# PiInTheSky-Mainboard-v2_3.net
KiCad netlist of a schematic drawn in EAGLE
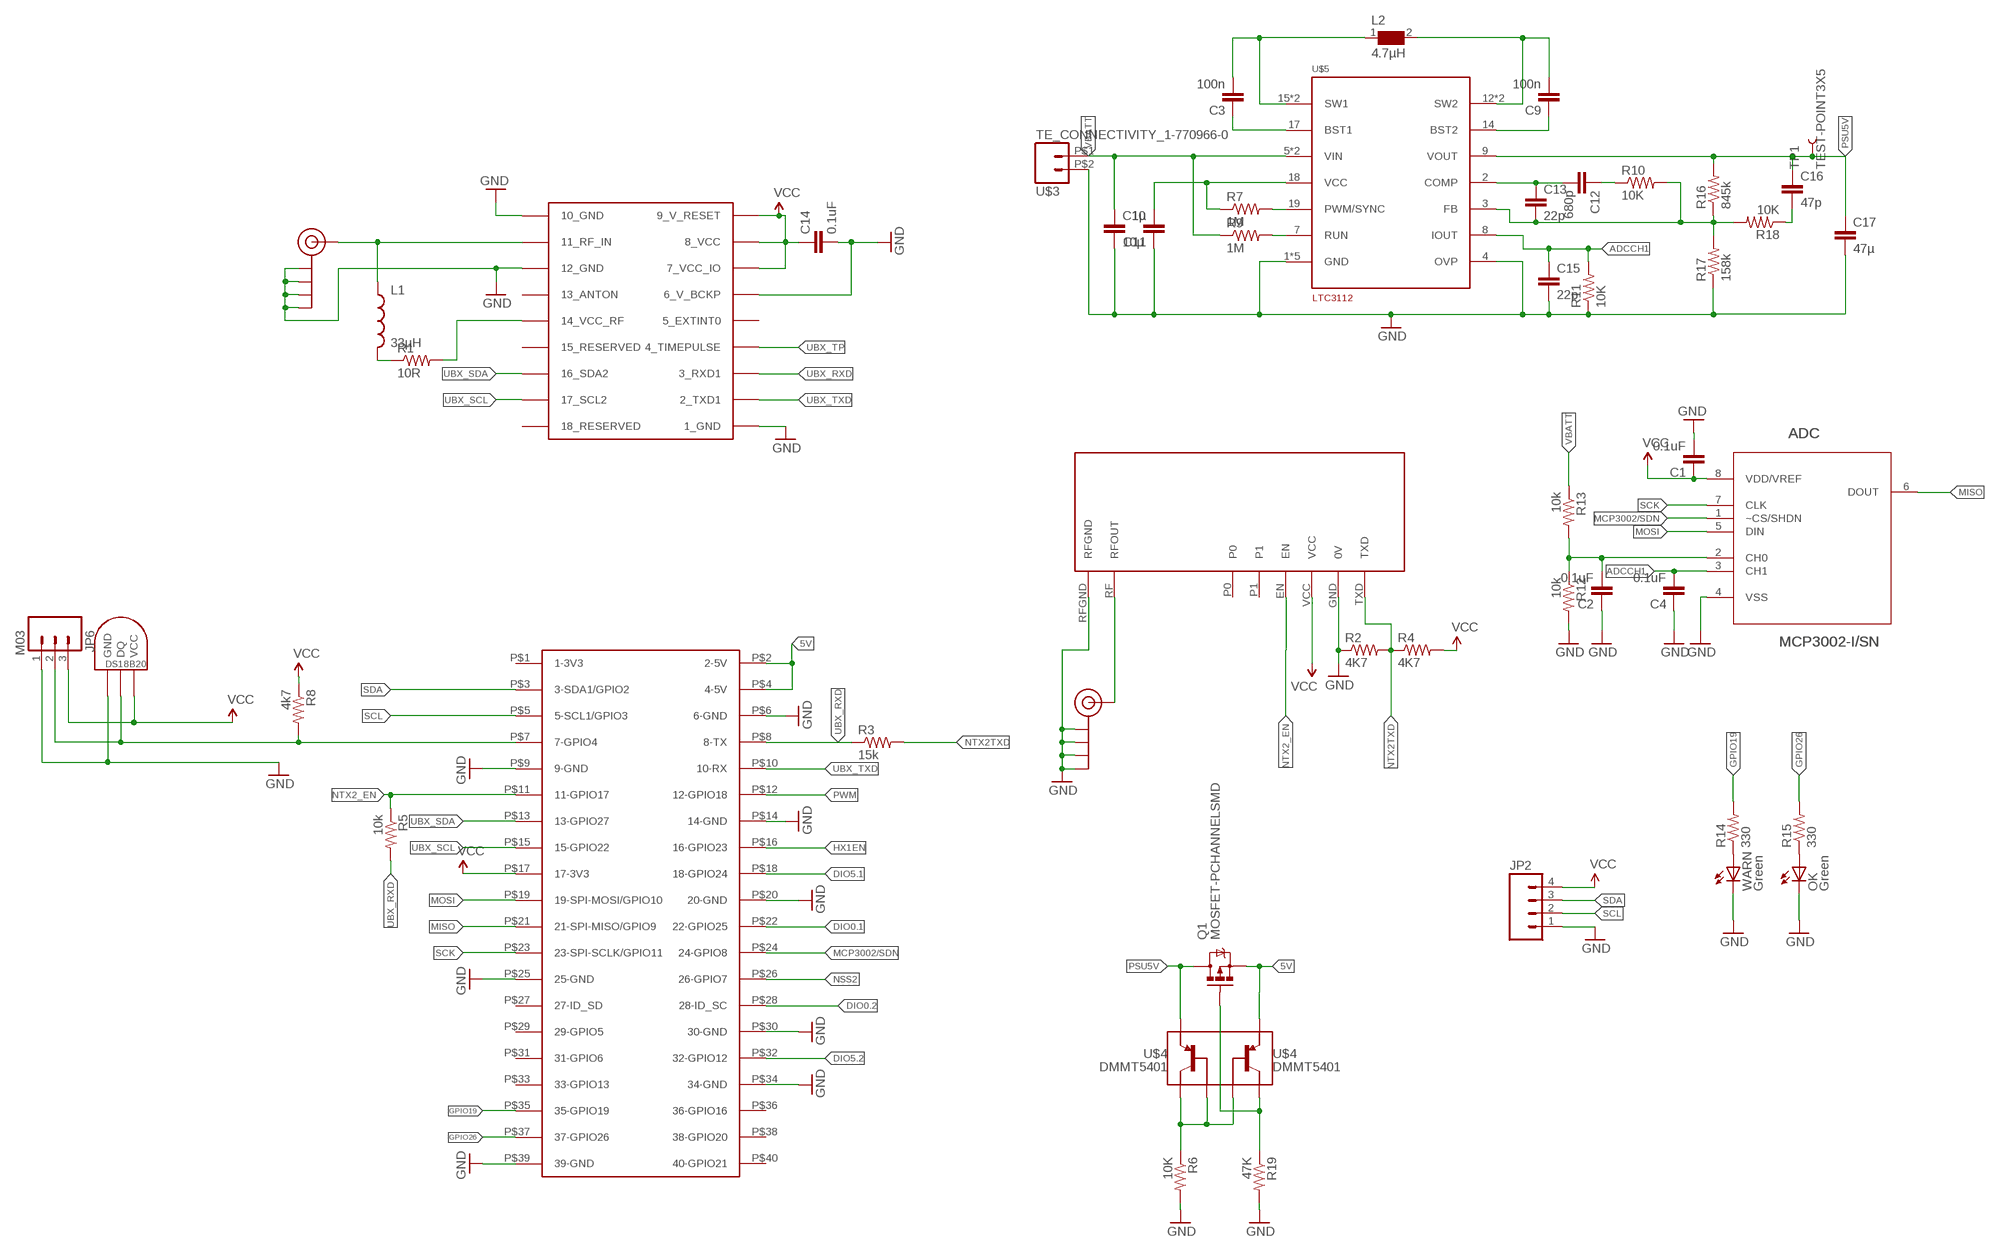
[diagram p0: schematic, sheet 1]

(export (version "E")
  (design (tool "Eeschema 10.0.6"))
  (components
    (comp (ref "ADC")
      (value "MCP3002-I/SN")
      (footprint "eagle-import:SOIC127P600X175-8N")
      (libsource (lib "eagle-import") (part "MCP3002-I/SN"))
    )
    (comp (ref "C1")
      (value "0.1uF")
      (footprint "eagle-import:0603-CAP")
      (libsource (lib "eagle-import") (part "CAP0603-CAP"))
    )
    (comp (ref "C2")
      (value "0.1uF")
      (footprint "eagle-import:0603-CAP")
      (libsource (lib "eagle-import") (part "CAP0603-CAP"))
    )
    (comp (ref "C3")
      (value "100n")
      (footprint "eagle-import:0603-CAP")
      (libsource (lib "eagle-import") (part "CAP0603-CAP"))
    )
    (comp (ref "C4")
      (value "0.1uF")
      (footprint "eagle-import:0603-CAP")
      (libsource (lib "eagle-import") (part "CAP0603-CAP"))
    )
    (comp (ref "C9")
      (value "100n")
      (footprint "eagle-import:0603-CAP")
      (libsource (lib "eagle-import") (part "CAP0603-CAP"))
    )
    (comp (ref "C10")
      (value "10µ")
      (footprint "eagle-import:1206")
      (libsource (lib "eagle-import") (part "CAP1206"))
    )
    (comp (ref "C11")
      (value "1µ")
      (footprint "eagle-import:0603-CAP")
      (libsource (lib "eagle-import") (part "CAP0603-CAP"))
    )
    (comp (ref "C12")
      (value "680p")
      (footprint "eagle-import:0603-CAP")
      (libsource (lib "eagle-import") (part "CAP0603-CAP"))
    )
    (comp (ref "C13")
      (value "22p")
      (footprint "eagle-import:0603-CAP")
      (libsource (lib "eagle-import") (part "CAP0603-CAP"))
    )
    (comp (ref "C14")
      (value "0.1uF")
      (footprint "eagle-import:0603-CAP")
      (libsource (lib "eagle-import") (part "CAP0603-CAP"))
    )
    (comp (ref "C15")
      (value "22p")
      (footprint "eagle-import:0603-CAP")
      (libsource (lib "eagle-import") (part "CAP0603-CAP"))
    )
    (comp (ref "C16")
      (value "47p")
      (footprint "eagle-import:0603-CAP")
      (libsource (lib "eagle-import") (part "CAP0603-CAP"))
    )
    (comp (ref "C17")
      (value "47µ")
      (footprint "eagle-import:1206")
      (libsource (lib "eagle-import") (part "CAP1206"))
    )
    (comp (ref "J$1")
      (value "SMA_EDGE")
      (footprint "eagle-import:SMA-EDGE")
      (libsource (lib "eagle-import") (part "SMA_EDGE"))
    )
    (comp (ref "J$2")
      (value "SMA_EDGE")
      (footprint "eagle-import:SMA-EDGE")
      (libsource (lib "eagle-import") (part "SMA_EDGE"))
    )
    (comp (ref "JP2")
      (value "M04PTH")
      (footprint "eagle-import:1X04")
      (libsource (lib "eagle-import") (part "M04PTH"))
    )
    (comp (ref "JP6")
      (value "M03")
      (footprint "eagle-import:M03-JST")
      (libsource (lib "eagle-import") (part "M03"))
    )
    (comp (ref "L1")
      (value "33µH")
      (footprint "eagle-import:0603")
      (libsource (lib "eagle-import") (part "INDUCTOR0603"))
    )
    (comp (ref "L2")
      (value "4.7µH")
      (footprint "eagle-import:WE-HCI_7030_7040_7050")
      (fields (field (name "MPN") "744311470"))
      (libsource (lib "eagle-import") (part "WE-HCI_7030/7040/7050-744311470"))
    )
    (comp (ref "OK")
      (value "Green")
      (footprint "eagle-import:LED-0603")
      (libsource (lib "eagle-import") (part "LED0603"))
    )
    (comp (ref "Q1")
      (value "MOSFET-PCHANNELSMD")
      (footprint "eagle-import:SOT23-3")
      (libsource (lib "eagle-import") (part "MOSFET-PCHANNELSMD"))
    )
    (comp (ref "R1")
      (value "10R")
      (footprint "eagle-import:0603-RES")
      (libsource (lib "eagle-import") (part "RESISTOR0603-RES"))
    )
    (comp (ref "R2")
      (value "4K7")
      (footprint "eagle-import:0603-RES")
      (libsource (lib "eagle-import") (part "RESISTOR0603-RES"))
    )
    (comp (ref "R3")
      (value "15k")
      (footprint "eagle-import:0603-RES")
      (libsource (lib "eagle-import") (part "RESISTOR0603-RES"))
    )
    (comp (ref "R4")
      (value "4K7")
      (footprint "eagle-import:0603-RES")
      (libsource (lib "eagle-import") (part "RESISTOR0603-RES"))
    )
    (comp (ref "R5")
      (value "10k")
      (footprint "eagle-import:0603-RES")
      (libsource (lib "eagle-import") (part "RESISTOR0603-RES"))
    )
    (comp (ref "R6")
      (value "10K")
      (footprint "eagle-import:0603-RES")
      (libsource (lib "eagle-import") (part "RESISTOR0603-RES"))
    )
    (comp (ref "R7")
      (value "1M")
      (footprint "eagle-import:0603-RES")
      (libsource (lib "eagle-import") (part "RESISTOR0603-RES"))
    )
    (comp (ref "R8")
      (value "4k7")
      (footprint "eagle-import:0603-RES")
      (libsource (lib "eagle-import") (part "RESISTOR0603-RES"))
    )
    (comp (ref "R9")
      (value "1M")
      (footprint "eagle-import:0603-RES")
      (libsource (lib "eagle-import") (part "RESISTOR0603-RES"))
    )
    (comp (ref "R10")
      (value "10K")
      (footprint "eagle-import:0603-RES")
      (libsource (lib "eagle-import") (part "RESISTOR0603-RES"))
    )
    (comp (ref "R11")
      (value "10K")
      (footprint "eagle-import:0603-RES")
      (libsource (lib "eagle-import") (part "RESISTOR0603-RES"))
    )
    (comp (ref "R12")
      (value "10k")
      (footprint "eagle-import:0603-RES")
      (libsource (lib "eagle-import") (part "RESISTOR0603-RES"))
    )
    (comp (ref "R13")
      (value "10k")
      (footprint "eagle-import:0603-RES")
      (libsource (lib "eagle-import") (part "RESISTOR0603-RES"))
    )
    (comp (ref "R14")
      (value "330")
      (footprint "eagle-import:0603-RES")
      (libsource (lib "eagle-import") (part "RESISTOR0603-RES"))
    )
    (comp (ref "R15")
      (value "330")
      (footprint "eagle-import:0603-RES")
      (libsource (lib "eagle-import") (part "RESISTOR0603-RES"))
    )
    (comp (ref "R16")
      (value "845k")
      (footprint "eagle-import:0603-RES")
      (libsource (lib "eagle-import") (part "RESISTOR0603-RES"))
    )
    (comp (ref "R17")
      (value "158k")
      (footprint "eagle-import:0603-RES")
      (libsource (lib "eagle-import") (part "RESISTOR0603-RES"))
    )
    (comp (ref "R18")
      (value "10K")
      (footprint "eagle-import:0603-RES")
      (libsource (lib "eagle-import") (part "RESISTOR0603-RES"))
    )
    (comp (ref "R19")
      (value "47K")
      (footprint "eagle-import:0603-RES")
      (libsource (lib "eagle-import") (part "RESISTOR0603-RES"))
    )
    (comp (ref "TEMP")
      (value "DS1821")
      (footprint "eagle-import:DS18B20_SOIC")
      (libsource (lib "eagle-import") (part "DS1820SOIC"))
    )
    (comp (ref "TP1")
      (value "TEST-POINT3X5")
      (footprint "eagle-import:PAD.03X.05")
      (libsource (lib "eagle-import") (part "TEST-POINT3X5"))
    )
    (comp (ref "U$1")
      (value "RASPBERRY-PI+")
      (footprint "eagle-import:RASPBERRY-PI-PLUS-CAM_NOTCH")
      (libsource (lib "eagle-import") (part "RASPBERRY-PI+"))
    )
    (comp (ref "U$3")
      (value "TE_CONNECTIVITY_1-770966-0")
      (footprint "eagle-import:TE_CONNECTIVITY_1-770966-0")
      (libsource (lib "eagle-import") (part "TE_CONNECTIVITY_1-770966-0"))
    )
    (comp (ref "U$4")
      (value "DMMT5401")
      (footprint "eagle-import:SOT26")
      (libsource (lib "eagle-import") (part "DMMT5401"))
    )
    (comp (ref "U$5")
      (value "LTC3112")
      (footprint "eagle-import:TSSOP-20")
      (libsource (lib "eagle-import") (part "LTC3112"))
    )
    (comp (ref "U$7")
      (value "UBLOX_MAX")
      (footprint "eagle-import:UBLOX_MAX")
      (libsource (lib "eagle-import") (part "UBLOX_MAX"))
    )
    (comp (ref "U$8")
      (value "RADIOMETRIX-MTX2")
      (footprint "eagle-import:RADIOMETRIX-MTX2")
      (libsource (lib "eagle-import") (part "RADIOMETRIX-MTX2"))
    )
    (comp (ref "WARN")
      (value "Green")
      (footprint "eagle-import:LED-0603")
      (libsource (lib "eagle-import") (part "LED0603"))
    )
  )
  (nets
    (net (code "1") (name "5V") (class "Default")
      (node (ref "Q1") (pin "2") (pinfunction "S_2") (pintype "passive"))
      (node (ref "U$1") (pin "P$2") (pinfunction "2-5V_P$2") (pintype "bidirectional"))
      (node (ref "U$1") (pin "P$4") (pinfunction "4-5V_P$4") (pintype "bidirectional"))
      (node (ref "U$4") (pin "5") (pinfunction "E2_5") (pintype "passive"))
    )
    (net (code "2") (name "ADCCH1") (class "Default")
      (node (ref "ADC") (pin "3") (pinfunction "CH1_3") (pintype "input"))
      (node (ref "C15") (pin "1") (pinfunction "1_1") (pintype "passive"))
      (node (ref "C4") (pin "2") (pinfunction "2_2") (pintype "passive"))
      (node (ref "R11") (pin "2") (pinfunction "2_2") (pintype "passive"))
      (node (ref "U$5") (pin "8") (pinfunction "IOUT_8") (pintype "bidirectional"))
    )
    (net (code "3") (name "DIO0.1") (class "Default")
      (node (ref "U$1") (pin "P$22") (pinfunction "22-GPIO25_P$22") (pintype "bidirectional"))
    )
    (net (code "4") (name "DIO0.2") (class "Default")
      (node (ref "U$1") (pin "P$28") (pinfunction "28-ID_SC_P$28") (pintype "bidirectional"))
    )
    (net (code "5") (name "DIO5.1") (class "Default")
      (node (ref "U$1") (pin "P$18") (pinfunction "18-GPIO24_P$18") (pintype "bidirectional"))
    )
    (net (code "6") (name "DIO5.2") (class "Default")
      (node (ref "U$1") (pin "P$32") (pinfunction "32-GPIO12_P$32") (pintype "bidirectional"))
    )
    (net (code "7") (name "GND") (class "Default")
      (node (ref "ADC") (pin "4") (pinfunction "VSS_4") (pintype "power_in"))
      (node (ref "C1") (pin "2") (pinfunction "2_2") (pintype "passive"))
      (node (ref "C10") (pin "2") (pinfunction "2_2") (pintype "passive"))
      (node (ref "C11") (pin "1") (pinfunction "1_1") (pintype "passive"))
      (node (ref "C14") (pin "2") (pinfunction "2_2") (pintype "passive"))
      (node (ref "C15") (pin "2") (pinfunction "2_2") (pintype "passive"))
      (node (ref "C17") (pin "2") (pinfunction "2_2") (pintype "passive"))
      (node (ref "C2") (pin "1") (pinfunction "1_1") (pintype "passive"))
      (node (ref "C4") (pin "1") (pinfunction "1_1") (pintype "passive"))
      (node (ref "J$1") (pin "GND@0") (pinfunction "GND_GND@0") (pintype "bidirectional"))
      (node (ref "J$1") (pin "GND@1") (pinfunction "GND_GND@1") (pintype "bidirectional"))
      (node (ref "J$1") (pin "GND@2") (pinfunction "GND_GND@2") (pintype "bidirectional"))
      (node (ref "J$1") (pin "GND@3") (pinfunction "GND_GND@3") (pintype "bidirectional"))
      (node (ref "J$2") (pin "GND@0") (pinfunction "GND_GND@0") (pintype "bidirectional"))
      (node (ref "J$2") (pin "GND@1") (pinfunction "GND_GND@1") (pintype "bidirectional"))
      (node (ref "J$2") (pin "GND@2") (pinfunction "GND_GND@2") (pintype "bidirectional"))
      (node (ref "J$2") (pin "GND@3") (pinfunction "GND_GND@3") (pintype "bidirectional"))
      (node (ref "JP2") (pin "1") (pinfunction "1_1") (pintype "passive"))
      (node (ref "JP6") (pin "1") (pinfunction "1_1") (pintype "passive"))
      (node (ref "OK") (pin "C") (pinfunction "C_C") (pintype "passive"))
      (node (ref "R11") (pin "1") (pinfunction "1_1") (pintype "passive"))
      (node (ref "R12") (pin "2") (pinfunction "2_2") (pintype "passive"))
      (node (ref "R17") (pin "1") (pinfunction "1_1") (pintype "passive"))
      (node (ref "R19") (pin "2") (pinfunction "2_2") (pintype "passive"))
      (node (ref "R2") (pin "1") (pinfunction "1_1") (pintype "passive"))
      (node (ref "R6") (pin "2") (pinfunction "2_2") (pintype "passive"))
      (node (ref "TEMP") (pin "GND") (pinfunction "GND_GND") (pintype "power_in"))
      (node (ref "U$1") (pin "P$14") (pinfunction "14-GND_P$14") (pintype "bidirectional"))
      (node (ref "U$1") (pin "P$20") (pinfunction "20-GND_P$20") (pintype "bidirectional"))
      (node (ref "U$1") (pin "P$25") (pinfunction "25-GND_P$25") (pintype "bidirectional"))
      (node (ref "U$1") (pin "P$30") (pinfunction "30-GND_P$30") (pintype "bidirectional"))
      (node (ref "U$1") (pin "P$34") (pinfunction "34-GND_P$34") (pintype "bidirectional"))
      (node (ref "U$1") (pin "P$39") (pinfunction "39-GND_P$39") (pintype "bidirectional"))
      (node (ref "U$1") (pin "P$6") (pinfunction "6-GND_P$6") (pintype "bidirectional"))
      (node (ref "U$1") (pin "P$9") (pinfunction "9-GND_P$9") (pintype "bidirectional"))
      (node (ref "U$3") (pin "P$2") (pinfunction "2_P$2") (pintype "passive"))
      (node (ref "U$5") (pin "1") (pinfunction "GND_1") (pintype "bidirectional"))
      (node (ref "U$5") (pin "10") (pinfunction "GND_10") (pintype "bidirectional"))
      (node (ref "U$5") (pin "11") (pinfunction "GND_11") (pintype "bidirectional"))
      (node (ref "U$5") (pin "20") (pinfunction "GND_20") (pintype "bidirectional"))
      (node (ref "U$5") (pin "21") (pinfunction "GND_21") (pintype "bidirectional"))
      (node (ref "U$5") (pin "4") (pinfunction "OVP_4") (pintype "bidirectional"))
      (node (ref "U$7") (pin "10_GND") (pinfunction "10_GND_10_GND") (pintype "power_in"))
      (node (ref "U$7") (pin "12_GND") (pinfunction "12_GND_12_GND") (pintype "power_in"))
      (node (ref "U$7") (pin "1_GND") (pinfunction "1_GND_1_GND") (pintype "power_in"))
      (node (ref "U$7") (pin "6_V_BCKP") (pinfunction "6_V_BCKP_6_V_BCKP") (pintype "bidirectional"))
      (node (ref "U$8") (pin "GND") (pinfunction "0V_GND") (pintype "bidirectional"))
      (node (ref "U$8") (pin "RFGND") (pinfunction "RFGND_RFGND") (pintype "bidirectional"))
      (node (ref "WARN") (pin "C") (pinfunction "C_C") (pintype "passive"))
    )
    (net (code "8") (name "GPIO19") (class "Default")
      (node (ref "R14") (pin "2") (pinfunction "2_2") (pintype "passive"))
      (node (ref "U$1") (pin "P$35") (pinfunction "35-GPIO19_P$35") (pintype "bidirectional"))
    )
    (net (code "9") (name "GPIO26") (class "Default")
      (node (ref "R15") (pin "2") (pinfunction "2_2") (pintype "passive"))
      (node (ref "U$1") (pin "P$37") (pinfunction "37-GPIO26_P$37") (pintype "bidirectional"))
    )
    (net (code "10") (name "HX1EN") (class "Default")
      (node (ref "U$1") (pin "P$16") (pinfunction "16-GPIO23_P$16") (pintype "bidirectional"))
    )
    (net (code "11") (name "MCP3002{slash}SDN") (class "Default")
      (node (ref "ADC") (pin "1") (pinfunction "~{CS/SHDN}_1") (pintype "input"))
      (node (ref "U$1") (pin "P$24") (pinfunction "24-GPIO8_P$24") (pintype "bidirectional"))
    )
    (net (code "12") (name "MISO") (class "Default")
      (node (ref "ADC") (pin "6") (pinfunction "DOUT_6") (pintype "output"))
      (node (ref "U$1") (pin "P$21") (pinfunction "21-SPI-MISO/GPIO9_P$21") (pintype "bidirectional"))
    )
    (net (code "13") (name "MOSI") (class "Default")
      (node (ref "ADC") (pin "5") (pinfunction "DIN_5") (pintype "input"))
      (node (ref "U$1") (pin "P$19") (pinfunction "19-SPI-MOSI/GPIO10_P$19") (pintype "bidirectional"))
    )
    (net (code "14") (name "NSS2") (class "Default")
      (node (ref "U$1") (pin "P$26") (pinfunction "26-GPIO7_P$26") (pintype "bidirectional"))
    )
    (net (code "15") (name "NTX2TXD") (class "Default")
      (node (ref "R2") (pin "2") (pinfunction "2_2") (pintype "passive"))
      (node (ref "R3") (pin "2") (pinfunction "2_2") (pintype "passive"))
      (node (ref "R4") (pin "1") (pinfunction "1_1") (pintype "passive"))
      (node (ref "U$8") (pin "TXD") (pinfunction "TXD_TXD") (pintype "bidirectional"))
    )
    (net (code "16") (name "NTX2_EN") (class "Default")
      (node (ref "R5") (pin "1") (pinfunction "1_1") (pintype "passive"))
      (node (ref "U$1") (pin "P$11") (pinfunction "11-GPIO17_P$11") (pintype "bidirectional"))
      (node (ref "U$8") (pin "EN") (pinfunction "EN_EN") (pintype "bidirectional"))
    )
    (net (code "17") (name "Net-(ADC-CH0)") (class "Default")
      (node (ref "ADC") (pin "2") (pinfunction "CH0_2") (pintype "input"))
      (node (ref "C2") (pin "2") (pinfunction "2_2") (pintype "passive"))
      (node (ref "R12") (pin "1") (pinfunction "1_1") (pintype "passive"))
      (node (ref "R13") (pin "2") (pinfunction "2_2") (pintype "passive"))
    )
    (net (code "18") (name "Net-(C3-Pad2)") (class "Default")
      (node (ref "C3") (pin "2") (pinfunction "2_2") (pintype "passive"))
      (node (ref "L2") (pin "1") (pinfunction "1_1") (pintype "passive"))
      (node (ref "U$5") (pin "15") (pinfunction "SW1_15") (pintype "bidirectional"))
      (node (ref "U$5") (pin "16") (pinfunction "SW1_16") (pintype "bidirectional"))
    )
    (net (code "19") (name "Net-(C9-Pad2)") (class "Default")
      (node (ref "C9") (pin "2") (pinfunction "2_2") (pintype "passive"))
      (node (ref "L2") (pin "2") (pinfunction "2_2") (pintype "passive"))
      (node (ref "U$5") (pin "12") (pinfunction "SW2_12") (pintype "bidirectional"))
      (node (ref "U$5") (pin "13") (pinfunction "SW2_13") (pintype "bidirectional"))
    )
    (net (code "20") (name "Net-(C12-Pad1)") (class "Default")
      (node (ref "C12") (pin "1") (pinfunction "1_1") (pintype "passive"))
      (node (ref "R10") (pin "1") (pinfunction "1_1") (pintype "passive"))
    )
    (net (code "21") (name "Net-(C16-Pad2)") (class "Default")
      (node (ref "C16") (pin "2") (pinfunction "2_2") (pintype "passive"))
      (node (ref "R18") (pin "1") (pinfunction "1_1") (pintype "passive"))
    )
    (net (code "22") (name "Net-(J$1-SIGNAL)") (class "Default")
      (node (ref "J$1") (pin "SIG") (pinfunction "SIGNAL_SIG") (pintype "bidirectional"))
      (node (ref "L1") (pin "1") (pinfunction "1_1") (pintype "passive"))
      (node (ref "U$7") (pin "11_RF_IN") (pinfunction "11_RF_IN_11_RF_IN") (pintype "bidirectional"))
    )
    (net (code "23") (name "Net-(J$2-SIGNAL)") (class "Default")
      (node (ref "J$2") (pin "SIG") (pinfunction "SIGNAL_SIG") (pintype "bidirectional"))
      (node (ref "U$8") (pin "RF") (pinfunction "RFOUT_RF") (pintype "bidirectional"))
    )
    (net (code "24") (name "Net-(L1-Pad2)") (class "Default")
      (node (ref "L1") (pin "2") (pinfunction "2_2") (pintype "passive"))
      (node (ref "R1") (pin "1") (pinfunction "1_1") (pintype "passive"))
    )
    (net (code "25") (name "Net-(OK-PadA)") (class "Default")
      (node (ref "OK") (pin "A") (pinfunction "A_A") (pintype "passive"))
      (node (ref "R15") (pin "1") (pinfunction "1_1") (pintype "passive"))
    )
    (net (code "26") (name "Net-(Q1-G)") (class "Default")
      (node (ref "Q1") (pin "1") (pinfunction "G_1") (pintype "passive"))
      (node (ref "R19") (pin "1") (pinfunction "1_1") (pintype "passive"))
      (node (ref "U$4") (pin "4") (pinfunction "C2_4") (pintype "passive"))
    )
    (net (code "27") (name "Net-(R1-Pad2)") (class "Default")
      (node (ref "R1") (pin "2") (pinfunction "2_2") (pintype "passive"))
      (node (ref "U$7") (pin "14_VCC_RF") (pinfunction "14_VCC_RF_14_VCC_RF") (pintype "bidirectional"))
    )
    (net (code "28") (name "Net-(R14-Pad1)") (class "Default")
      (node (ref "R14") (pin "1") (pinfunction "1_1") (pintype "passive"))
      (node (ref "WARN") (pin "A") (pinfunction "A_A") (pintype "passive"))
    )
    (net (code "29") (name "Net-(U$1-7-GPIO4)") (class "Default")
      (node (ref "JP6") (pin "2") (pinfunction "2_2") (pintype "passive"))
      (node (ref "R8") (pin "2") (pinfunction "2_2") (pintype "passive"))
      (node (ref "TEMP") (pin "DQ") (pinfunction "DQ_DQ") (pintype "bidirectional"))
      (node (ref "U$1") (pin "P$7") (pinfunction "7-GPIO4_P$7") (pintype "bidirectional"))
    )
    (net (code "30") (name "Net-(U$4-B1)") (class "Default")
      (node (ref "R6") (pin "1") (pinfunction "1_1") (pintype "passive"))
      (node (ref "U$4") (pin "1") (pinfunction "C1_1") (pintype "passive"))
      (node (ref "U$4") (pin "2") (pinfunction "B1_2") (pintype "passive"))
      (node (ref "U$4") (pin "3") (pinfunction "B2_3") (pintype "passive"))
    )
    (net (code "31") (name "Net-(U$5-BST1)") (class "Default")
      (node (ref "C3") (pin "1") (pinfunction "1_1") (pintype "passive"))
      (node (ref "U$5") (pin "17") (pinfunction "BST1_17") (pintype "bidirectional"))
    )
    (net (code "32") (name "Net-(U$5-BST2)") (class "Default")
      (node (ref "C9") (pin "1") (pinfunction "1_1") (pintype "passive"))
      (node (ref "U$5") (pin "14") (pinfunction "BST2_14") (pintype "bidirectional"))
    )
    (net (code "33") (name "Net-(U$5-COMP)") (class "Default")
      (node (ref "C12") (pin "2") (pinfunction "2_2") (pintype "passive"))
      (node (ref "C13") (pin "1") (pinfunction "1_1") (pintype "passive"))
      (node (ref "U$5") (pin "2") (pinfunction "COMP_2") (pintype "bidirectional"))
    )
    (net (code "34") (name "Net-(U$5-FB)") (class "Default")
      (node (ref "C13") (pin "2") (pinfunction "2_2") (pintype "passive"))
      (node (ref "R10") (pin "2") (pinfunction "2_2") (pintype "passive"))
      (node (ref "R16") (pin "1") (pinfunction "1_1") (pintype "passive"))
      (node (ref "R17") (pin "2") (pinfunction "2_2") (pintype "passive"))
      (node (ref "R18") (pin "2") (pinfunction "2_2") (pintype "passive"))
      (node (ref "U$5") (pin "3") (pinfunction "FB_3") (pintype "bidirectional"))
    )
    (net (code "35") (name "Net-(U$5-PWM{slash}SYNC)") (class "Default")
      (node (ref "R7") (pin "2") (pinfunction "2_2") (pintype "passive"))
      (node (ref "U$5") (pin "19") (pinfunction "PWM/SYNC_19") (pintype "bidirectional"))
    )
    (net (code "36") (name "Net-(U$5-RUN)") (class "Default")
      (node (ref "R9") (pin "2") (pinfunction "2_2") (pintype "passive"))
      (node (ref "U$5") (pin "7") (pinfunction "RUN_7") (pintype "bidirectional"))
    )
    (net (code "37") (name "Net-(U$5-VCC)") (class "Default")
      (node (ref "C11") (pin "2") (pinfunction "2_2") (pintype "passive"))
      (node (ref "R7") (pin "1") (pinfunction "1_1") (pintype "passive"))
      (node (ref "U$5") (pin "18") (pinfunction "VCC_18") (pintype "bidirectional"))
    )
    (net (code "38") (name "PSU5V") (class "Default")
      (node (ref "C16") (pin "1") (pinfunction "1_1") (pintype "passive"))
      (node (ref "C17") (pin "1") (pinfunction "1_1") (pintype "passive"))
      (node (ref "Q1") (pin "3") (pinfunction "D_3") (pintype "passive"))
      (node (ref "R16") (pin "2") (pinfunction "2_2") (pintype "passive"))
      (node (ref "TP1") (pin "P$1") (pinfunction "1_P$1") (pintype "bidirectional"))
      (node (ref "U$4") (pin "6") (pinfunction "E1_6") (pintype "passive"))
      (node (ref "U$5") (pin "9") (pinfunction "VOUT_9") (pintype "bidirectional"))
    )
    (net (code "39") (name "PWM") (class "Default")
      (node (ref "U$1") (pin "P$12") (pinfunction "12-GPIO18_P$12") (pintype "bidirectional"))
    )
    (net (code "40") (name "SCK") (class "Default")
      (node (ref "ADC") (pin "7") (pinfunction "CLK_7") (pintype "input"))
      (node (ref "U$1") (pin "P$23") (pinfunction "23-SPI-SCLK/GPIO11_P$23") (pintype "bidirectional"))
    )
    (net (code "41") (name "SCL") (class "Default")
      (node (ref "JP2") (pin "2") (pinfunction "2_2") (pintype "passive"))
      (node (ref "U$1") (pin "P$5") (pinfunction "5-SCL1/GPIO3_P$5") (pintype "bidirectional"))
    )
    (net (code "42") (name "SDA") (class "Default")
      (node (ref "JP2") (pin "3") (pinfunction "3_3") (pintype "passive"))
      (node (ref "U$1") (pin "P$3") (pinfunction "3-SDA1/GPIO2_P$3") (pintype "bidirectional"))
    )
    (net (code "43") (name "UBX_RXD") (class "Default")
      (node (ref "R3") (pin "1") (pinfunction "1_1") (pintype "passive"))
      (node (ref "R5") (pin "2") (pinfunction "2_2") (pintype "passive"))
      (node (ref "U$1") (pin "P$8") (pinfunction "8-TX_P$8") (pintype "bidirectional"))
      (node (ref "U$7") (pin "3_RXD1") (pinfunction "3_RXD1_3_RXD1") (pintype "bidirectional"))
    )
    (net (code "44") (name "UBX_SCL") (class "Default")
      (node (ref "U$1") (pin "P$15") (pinfunction "15-GPIO22_P$15") (pintype "bidirectional"))
      (node (ref "U$7") (pin "17_SCL2") (pinfunction "17_SCL2_17_SCL2") (pintype "bidirectional"))
    )
    (net (code "45") (name "UBX_SDA") (class "Default")
      (node (ref "U$1") (pin "P$13") (pinfunction "13-GPIO27_P$13") (pintype "bidirectional"))
      (node (ref "U$7") (pin "16_SDA2") (pinfunction "16_SDA2_16_SDA2") (pintype "bidirectional"))
    )
    (net (code "46") (name "UBX_TP") (class "Default")
      (node (ref "U$7") (pin "4_TIMEPULSE") (pinfunction "4_TIMEPULSE_4_TIMEPULSE") (pintype "bidirectional"))
    )
    (net (code "47") (name "UBX_TXD") (class "Default")
      (node (ref "U$1") (pin "P$10") (pinfunction "10-RX_P$10") (pintype "bidirectional"))
      (node (ref "U$7") (pin "2_TXD1") (pinfunction "2_TXD1_2_TXD1") (pintype "bidirectional"))
    )
    (net (code "48") (name "VBATT") (class "Default")
      (node (ref "C10") (pin "1") (pinfunction "1_1") (pintype "passive"))
      (node (ref "R13") (pin "1") (pinfunction "1_1") (pintype "passive"))
      (node (ref "R9") (pin "1") (pinfunction "1_1") (pintype "passive"))
      (node (ref "U$3") (pin "P$1") (pinfunction "1_P$1") (pintype "passive"))
      (node (ref "U$5") (pin "5") (pinfunction "VIN_5") (pintype "bidirectional"))
      (node (ref "U$5") (pin "6") (pinfunction "VIN_6") (pintype "bidirectional"))
    )
    (net (code "49") (name "VCC") (class "Default")
      (node (ref "ADC") (pin "8") (pinfunction "VDD/VREF_8") (pintype "power_in"))
      (node (ref "C1") (pin "1") (pinfunction "1_1") (pintype "passive"))
      (node (ref "C14") (pin "1") (pinfunction "1_1") (pintype "passive"))
      (node (ref "JP2") (pin "4") (pinfunction "4_4") (pintype "passive"))
      (node (ref "JP6") (pin "3") (pinfunction "3_3") (pintype "passive"))
      (node (ref "R4") (pin "2") (pinfunction "2_2") (pintype "passive"))
      (node (ref "R8") (pin "1") (pinfunction "1_1") (pintype "passive"))
      (node (ref "TEMP") (pin "VCC") (pinfunction "VCC_VCC") (pintype "power_in"))
      (node (ref "U$1") (pin "P$17") (pinfunction "17-3V3_P$17") (pintype "bidirectional"))
      (node (ref "U$7") (pin "7_VCC_IO") (pinfunction "7_VCC_IO_7_VCC_IO") (pintype "power_in"))
      (node (ref "U$7") (pin "8_VCC") (pinfunction "8_VCC_8_VCC") (pintype "power_in"))
      (node (ref "U$7") (pin "9_V_RESET") (pinfunction "9_V_RESET_9_V_RESET") (pintype "power_in"))
      (node (ref "U$8") (pin "VCC") (pinfunction "VCC_VCC") (pintype "bidirectional"))
    )
    (net (code "50") (name "unconnected-(U$1-1-3V3-PadP$1)") (class "Default")
      (node (ref "U$1") (pin "P$1") (pinfunction "1-3V3_P$1") (pintype "bidirectional"))
    )
    (net (code "51") (name "unconnected-(U$1-27-ID_SD-PadP$27)") (class "Default")
      (node (ref "U$1") (pin "P$27") (pinfunction "27-ID_SD_P$27") (pintype "bidirectional"))
    )
    (net (code "52") (name "unconnected-(U$1-29-GPIO5-PadP$29)") (class "Default")
      (node (ref "U$1") (pin "P$29") (pinfunction "29-GPIO5_P$29") (pintype "bidirectional"))
    )
    (net (code "53") (name "unconnected-(U$1-31-GPIO6-PadP$31)") (class "Default")
      (node (ref "U$1") (pin "P$31") (pinfunction "31-GPIO6_P$31") (pintype "bidirectional"))
    )
    (net (code "54") (name "unconnected-(U$1-33-GPIO13-PadP$33)") (class "Default")
      (node (ref "U$1") (pin "P$33") (pinfunction "33-GPIO13_P$33") (pintype "bidirectional"))
    )
    (net (code "55") (name "unconnected-(U$1-36-GPIO16-PadP$36)") (class "Default")
      (node (ref "U$1") (pin "P$36") (pinfunction "36-GPIO16_P$36") (pintype "bidirectional"))
    )
    (net (code "56") (name "unconnected-(U$1-38-GPIO20-PadP$38)") (class "Default")
      (node (ref "U$1") (pin "P$38") (pinfunction "38-GPIO20_P$38") (pintype "bidirectional"))
    )
    (net (code "57") (name "unconnected-(U$1-40-GPIO21-PadP$40)") (class "Default")
      (node (ref "U$1") (pin "P$40") (pinfunction "40-GPIO21_P$40") (pintype "bidirectional"))
    )
    (net (code "58") (name "unconnected-(U$7-Pad5_EXTINT0)") (class "Default")
      (node (ref "U$7") (pin "5_EXTINT0") (pinfunction "5_EXTINT0_5_EXTINT0") (pintype "bidirectional"))
    )
    (net (code "59") (name "unconnected-(U$7-Pad13_ANTON)") (class "Default")
      (node (ref "U$7") (pin "13_ANTON") (pinfunction "13_ANTON_13_ANTON") (pintype "bidirectional"))
    )
    (net (code "60") (name "unconnected-(U$7-Pad15_RESERVED)") (class "Default")
      (node (ref "U$7") (pin "15_RESERVED") (pinfunction "15_RESERVED_15_RESERVED") (pintype "bidirectional"))
    )
    (net (code "61") (name "unconnected-(U$7-Pad18_RESERVED)") (class "Default")
      (node (ref "U$7") (pin "18_RESERVED") (pinfunction "18_RESERVED_18_RESERVED") (pintype "bidirectional"))
    )
    (net (code "62") (name "unconnected-(U$8-PadP0)") (class "Default")
      (node (ref "U$8") (pin "P0") (pinfunction "P0_P0") (pintype "bidirectional"))
    )
    (net (code "63") (name "unconnected-(U$8-PadP1)") (class "Default")
      (node (ref "U$8") (pin "P1") (pinfunction "P1_P1") (pintype "bidirectional"))
    )
  )
)
